# 3phaseSim.net
KiCad netlist of a schematic drawn in Altium Designer
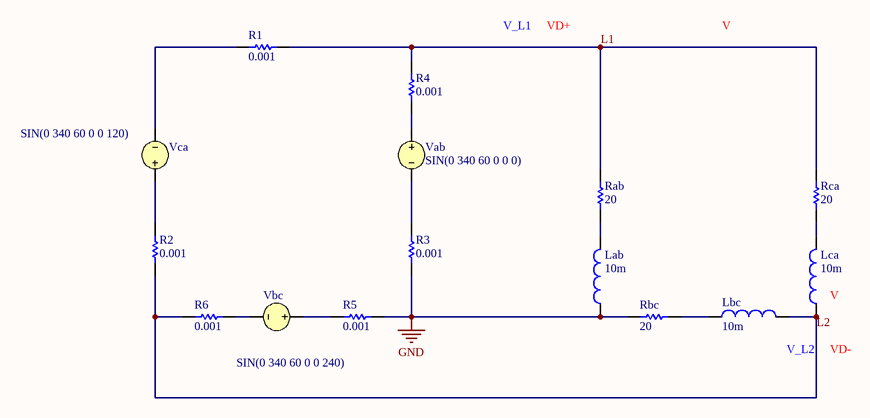
[diagram p0: 3phaseSim.SchDoc]

(export (version "E")
  (design (tool "Eeschema 10.0.6"))
  (components
    (comp (ref "Lab")
      (value "10m")
      (description "Inductor")
      (libsource (lib "Simulation Generic Components") (part "Inductor"))
    )
    (comp (ref "Lbc")
      (value "10m")
      (description "Inductor")
      (libsource (lib "Simulation Generic Components") (part "Inductor"))
    )
    (comp (ref "Lca")
      (value "10m")
      (description "Inductor")
      (libsource (lib "Simulation Generic Components") (part "Inductor"))
    )
    (comp (ref "R1")
      (value "0.001")
      (description "Resistor")
      (libsource (lib "Simulation Generic Components") (part "Resistor"))
    )
    (comp (ref "R2")
      (value "0.001")
      (description "Resistor")
      (libsource (lib "Simulation Generic Components") (part "Resistor"))
    )
    (comp (ref "R3")
      (value "0.001")
      (description "Resistor")
      (libsource (lib "Simulation Generic Components") (part "Resistor"))
    )
    (comp (ref "R4")
      (value "0.001")
      (description "Resistor")
      (libsource (lib "Simulation Generic Components") (part "Resistor"))
    )
    (comp (ref "R5")
      (value "0.001")
      (description "Resistor")
      (libsource (lib "Simulation Generic Components") (part "Resistor"))
    )
    (comp (ref "R6")
      (value "0.001")
      (description "Resistor")
      (libsource (lib "Simulation Generic Components") (part "Resistor"))
    )
    (comp (ref "Rab")
      (value "20")
      (description "Resistor")
      (libsource (lib "Simulation Generic Components") (part "Resistor"))
    )
    (comp (ref "Rbc")
      (value "20")
      (description "Resistor")
      (libsource (lib "Simulation Generic Components") (part "Resistor"))
    )
    (comp (ref "Rca")
      (value "20")
      (description "Resistor")
      (libsource (lib "Simulation Generic Components") (part "Resistor"))
    )
    (comp (ref "Vab")
      (value "SIN(0 340 60 0 0 0)")
      (description "Voltage Source")
      (fields (field (name "PUBLISHER") "Altium Limited"))
      (libsource (lib "Simulation Generic Components") (part "VSRC"))
    )
    (comp (ref "Vbc")
      (value "SIN(0 340 60 0 0 240)")
      (description "Voltage Source")
      (fields (field (name "PUBLISHER") "Altium Limited"))
      (libsource (lib "Simulation Generic Components") (part "VSRC"))
    )
    (comp (ref "Vca")
      (value "SIN(0 340 60 0 0 120)")
      (description "Voltage Source")
      (fields (field (name "PUBLISHER") "Altium Limited"))
      (libsource (lib "Simulation Generic Components") (part "VSRC"))
    )
  )
  (nets
    (net (code "1") (name "/L1") (class "Default")
      (node (ref "R1") (pin "2") (pinfunction "2_2") (pintype "passive"))
      (node (ref "R4") (pin "1") (pinfunction "1_1") (pintype "passive"))
      (node (ref "Rab") (pin "1") (pinfunction "1_1") (pintype "passive"))
      (node (ref "Rca") (pin "1") (pinfunction "1_1") (pintype "passive"))
    )
    (net (code "2") (name "/L2") (class "Default")
      (node (ref "Lbc") (pin "2") (pinfunction "2_2") (pintype "passive"))
      (node (ref "Lca") (pin "1") (pinfunction "1_1") (pintype "passive"))
      (node (ref "R2") (pin "1") (pinfunction "1_1") (pintype "passive"))
      (node (ref "R6") (pin "1") (pinfunction "1_1") (pintype "passive"))
    )
    (net (code "3") (name "GND") (class "Default")
      (node (ref "Lab") (pin "1") (pinfunction "1_1") (pintype "passive"))
      (node (ref "R3") (pin "1") (pinfunction "1_1") (pintype "passive"))
      (node (ref "R5") (pin "2") (pinfunction "2_2") (pintype "passive"))
      (node (ref "Rbc") (pin "2") (pinfunction "2_2") (pintype "passive"))
    )
    (net (code "4") (name "Net-(Lab-Pad2)") (class "Default")
      (node (ref "Lab") (pin "2") (pinfunction "2_2") (pintype "passive"))
      (node (ref "Rab") (pin "2") (pinfunction "2_2") (pintype "passive"))
    )
    (net (code "5") (name "Net-(Lbc-Pad1)") (class "Default")
      (node (ref "Lbc") (pin "1") (pinfunction "1_1") (pintype "passive"))
      (node (ref "Rbc") (pin "1") (pinfunction "1_1") (pintype "passive"))
    )
    (net (code "6") (name "Net-(Lca-Pad2)") (class "Default")
      (node (ref "Lca") (pin "2") (pinfunction "2_2") (pintype "passive"))
      (node (ref "Rca") (pin "2") (pinfunction "2_2") (pintype "passive"))
    )
    (net (code "7") (name "Net-(R1-Pad1)") (class "Default")
      (node (ref "R1") (pin "1") (pinfunction "1_1") (pintype "passive"))
      (node (ref "Vca") (pin "2") (pinfunction "2_2") (pintype "passive"))
    )
    (net (code "8") (name "Net-(R2-Pad2)") (class "Default")
      (node (ref "R2") (pin "2") (pinfunction "2_2") (pintype "passive"))
      (node (ref "Vca") (pin "1") (pinfunction "1_1") (pintype "passive"))
    )
    (net (code "9") (name "Net-(R3-Pad2)") (class "Default")
      (node (ref "R3") (pin "2") (pinfunction "2_2") (pintype "passive"))
      (node (ref "Vab") (pin "2") (pinfunction "2_2") (pintype "passive"))
    )
    (net (code "10") (name "Net-(R4-Pad2)") (class "Default")
      (node (ref "R4") (pin "2") (pinfunction "2_2") (pintype "passive"))
      (node (ref "Vab") (pin "1") (pinfunction "1_1") (pintype "passive"))
    )
    (net (code "11") (name "Net-(R5-Pad1)") (class "Default")
      (node (ref "R5") (pin "1") (pinfunction "1_1") (pintype "passive"))
      (node (ref "Vbc") (pin "1") (pinfunction "1_1") (pintype "passive"))
    )
    (net (code "12") (name "Net-(R6-Pad2)") (class "Default")
      (node (ref "R6") (pin "2") (pinfunction "2_2") (pintype "passive"))
      (node (ref "Vbc") (pin "2") (pinfunction "2_2") (pintype "passive"))
    )
  )
)
